# turbo.net
KiCad netlist of a schematic drawn in EAGLE
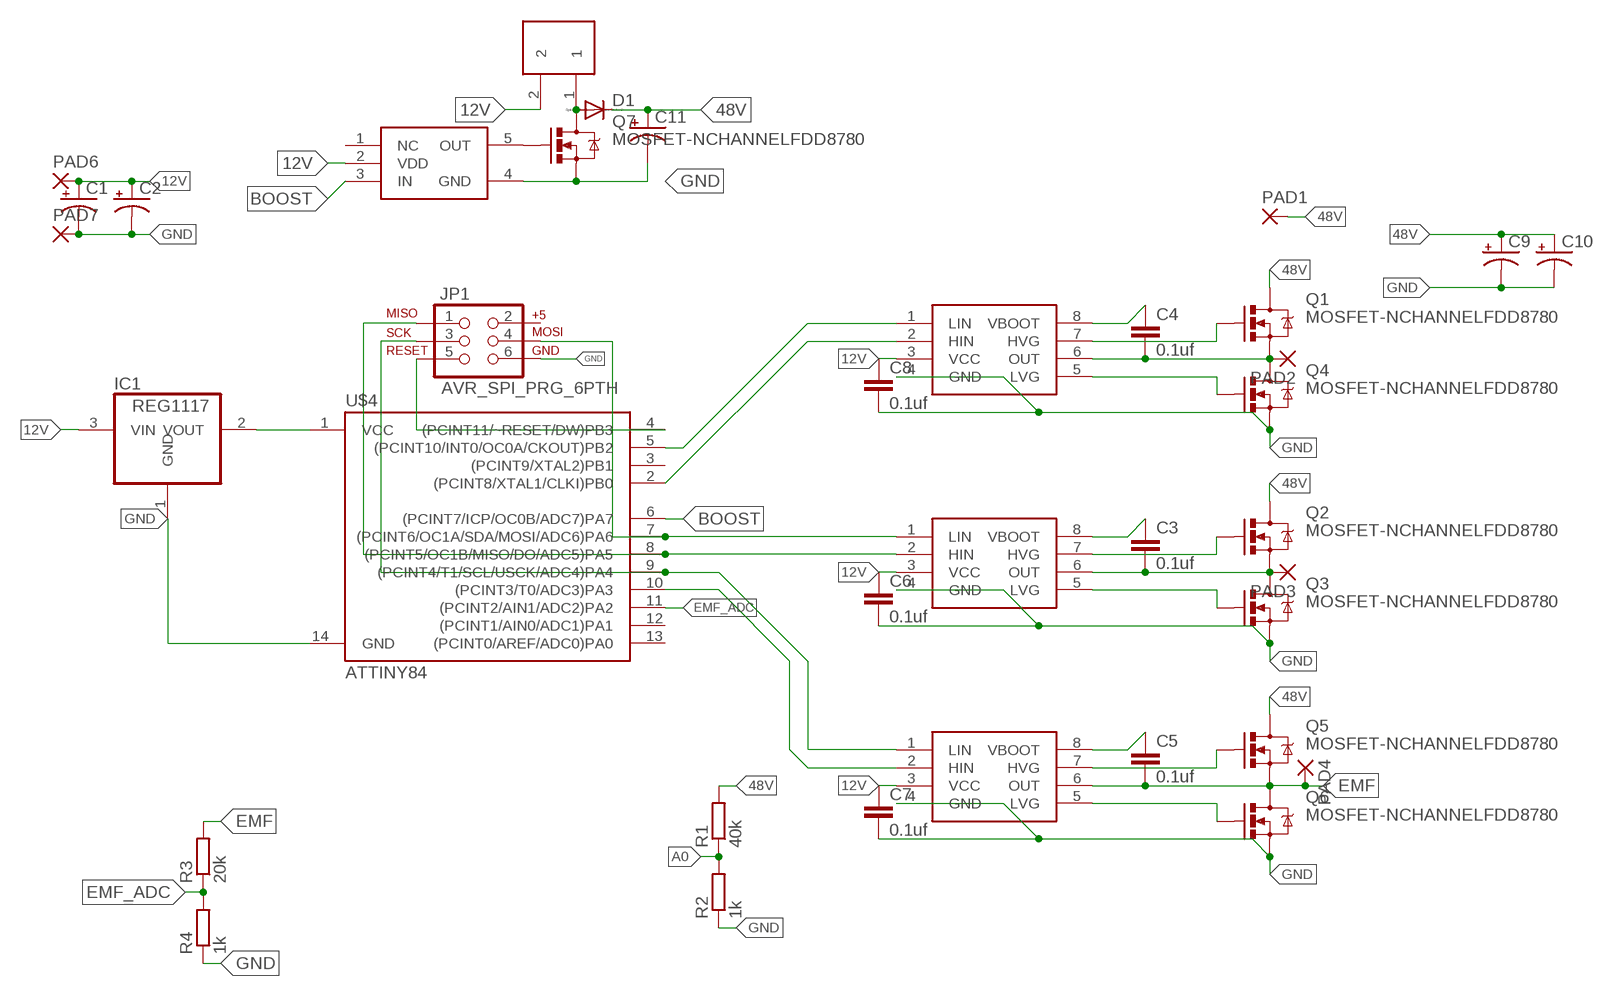
[diagram p0: schematic, sheet 1]

(export (version "E")
  (design (tool "Eeschema 10.0.6"))
  (components
    (comp (ref "C1")
      (value "CPOL-USE7.5-18")
      (footprint "eagle-import:E7,5-18")
      (libsource (lib "eagle-import") (part "CPOL-USE7.5-18"))
    )
    (comp (ref "C2")
      (value "CPOL-USE7.5-18")
      (footprint "eagle-import:E7,5-18")
      (libsource (lib "eagle-import") (part "CPOL-USE7.5-18"))
    )
    (comp (ref "C3")
      (value "0.1uf")
      (footprint "eagle-import:C0603")
      (libsource (lib "eagle-import") (part "C-EUC0603"))
    )
    (comp (ref "C4")
      (value "0.1uf")
      (footprint "eagle-import:C0603")
      (libsource (lib "eagle-import") (part "C-EUC0603"))
    )
    (comp (ref "C5")
      (value "0.1uf")
      (footprint "eagle-import:C0603")
      (libsource (lib "eagle-import") (part "C-EUC0603"))
    )
    (comp (ref "C6")
      (value "0.1uf")
      (footprint "eagle-import:C0603")
      (libsource (lib "eagle-import") (part "C-EUC0603"))
    )
    (comp (ref "C7")
      (value "0.1uf")
      (footprint "eagle-import:C0603")
      (libsource (lib "eagle-import") (part "C-EUC0603"))
    )
    (comp (ref "C8")
      (value "0.1uf")
      (footprint "eagle-import:C0603")
      (libsource (lib "eagle-import") (part "C-EUC0603"))
    )
    (comp (ref "C9")
      (value "CPOL-USE7.5-18")
      (footprint "eagle-import:E7,5-18")
      (libsource (lib "eagle-import") (part "CPOL-USE7.5-18"))
    )
    (comp (ref "C10")
      (value "CPOL-USE7.5-18")
      (footprint "eagle-import:E7,5-18")
      (libsource (lib "eagle-import") (part "CPOL-USE7.5-18"))
    )
    (comp (ref "C11")
      (value "CPOL-USE7.5-18")
      (footprint "eagle-import:E7,5-18")
      (libsource (lib "eagle-import") (part "CPOL-USE7.5-18"))
    )
    (comp (ref "D1")
      (value "DIODE-TO220V")
      (footprint "eagle-import:TO220ACS")
      (libsource (lib "eagle-import") (part "DIODE-TO220V"))
    )
    (comp (ref "IC1")
      (value "REG1117")
      (footprint "eagle-import:SOT223")
      (libsource (lib "eagle-import") (part "REG1117"))
    )
    (comp (ref "JP1")
      (value "AVR_SPI_PRG_6PTH")
      (footprint "eagle-import:2X3")
      (libsource (lib "eagle-import") (part "AVR_SPI_PRG_6PTH"))
    )
    (comp (ref "PAD1")
      (value "WIREPADSMD5-2,5")
      (footprint "eagle-import:5-2,5")
      (libsource (lib "eagle-import") (part "WIREPADSMD5-2,5"))
    )
    (comp (ref "PAD2")
      (value "WIREPADSMD5-2,5")
      (footprint "eagle-import:5-2,5")
      (libsource (lib "eagle-import") (part "WIREPADSMD5-2,5"))
    )
    (comp (ref "PAD3")
      (value "WIREPADSMD5-2,5")
      (footprint "eagle-import:5-2,5")
      (libsource (lib "eagle-import") (part "WIREPADSMD5-2,5"))
    )
    (comp (ref "PAD4")
      (value "WIREPADSMD5-2,5")
      (footprint "eagle-import:5-2,5")
      (libsource (lib "eagle-import") (part "WIREPADSMD5-2,5"))
    )
    (comp (ref "PAD6")
      (value "WIREPADSMD5-2,5")
      (footprint "eagle-import:5-2,5")
      (libsource (lib "eagle-import") (part "WIREPADSMD5-2,5"))
    )
    (comp (ref "PAD7")
      (value "WIREPADSMD5-2,5")
      (footprint "eagle-import:5-2,5")
      (libsource (lib "eagle-import") (part "WIREPADSMD5-2,5"))
    )
    (comp (ref "Q1")
      (value "MOSFET-NCHANNELFDD8780")
      (footprint "eagle-import:DPAK")
      (libsource (lib "eagle-import") (part "MOSFET-NCHANNELFDD8780"))
    )
    (comp (ref "Q2")
      (value "MOSFET-NCHANNELFDD8780")
      (footprint "eagle-import:DPAK")
      (libsource (lib "eagle-import") (part "MOSFET-NCHANNELFDD8780"))
    )
    (comp (ref "Q3")
      (value "MOSFET-NCHANNELFDD8780")
      (footprint "eagle-import:DPAK")
      (libsource (lib "eagle-import") (part "MOSFET-NCHANNELFDD8780"))
    )
    (comp (ref "Q4")
      (value "MOSFET-NCHANNELFDD8780")
      (footprint "eagle-import:DPAK")
      (libsource (lib "eagle-import") (part "MOSFET-NCHANNELFDD8780"))
    )
    (comp (ref "Q5")
      (value "MOSFET-NCHANNELFDD8780")
      (footprint "eagle-import:DPAK")
      (libsource (lib "eagle-import") (part "MOSFET-NCHANNELFDD8780"))
    )
    (comp (ref "Q6")
      (value "MOSFET-NCHANNELFDD8780")
      (footprint "eagle-import:DPAK")
      (libsource (lib "eagle-import") (part "MOSFET-NCHANNELFDD8780"))
    )
    (comp (ref "Q7")
      (value "MOSFET-NCHANNELFDD8780")
      (footprint "eagle-import:DPAK")
      (libsource (lib "eagle-import") (part "MOSFET-NCHANNELFDD8780"))
    )
    (comp (ref "R1")
      (value "40k")
      (footprint "eagle-import:R0603")
      (libsource (lib "eagle-import") (part "R-EU_R0603"))
    )
    (comp (ref "R2")
      (value "1k")
      (footprint "eagle-import:R0603")
      (libsource (lib "eagle-import") (part "R-EU_R0603"))
    )
    (comp (ref "R3")
      (value "20k")
      (footprint "eagle-import:R0603")
      (libsource (lib "eagle-import") (part "R-EU_R0603"))
    )
    (comp (ref "R4")
      (value "1k")
      (footprint "eagle-import:R0603")
      (libsource (lib "eagle-import") (part "R-EU_R0603"))
    )
    (comp (ref "U$1")
      (value "L6387")
      (footprint "eagle-import:SOIC8")
      (libsource (lib "eagle-import") (part "L6387"))
    )
    (comp (ref "U$2")
      (value "L6387")
      (footprint "eagle-import:SOIC8")
      (libsource (lib "eagle-import") (part "L6387"))
    )
    (comp (ref "U$3")
      (value "L6387")
      (footprint "eagle-import:SOIC8")
      (libsource (lib "eagle-import") (part "L6387"))
    )
    (comp (ref "U$4")
      (value "ATTINY84")
      (footprint "eagle-import:SO14")
      (libsource (lib "eagle-import") (part "ATTINY84"))
    )
    (comp (ref "U$5")
      (value "2310")
      (footprint "eagle-import:2310")
      (libsource (lib "eagle-import") (part "2310"))
    )
    (comp (ref "U$6")
      (value "MCP1415")
      (footprint "eagle-import:SOT23-5")
      (libsource (lib "eagle-import") (part "MCP1415"))
    )
  )
  (nets
    (net (code "1") (name "12V") (class "Default")
      (node (ref "C1") (pin "+") (pinfunction "+_+") (pintype "passive"))
      (node (ref "C2") (pin "+") (pinfunction "+_+") (pintype "passive"))
      (node (ref "C6") (pin "1") (pinfunction "1_1") (pintype "passive"))
      (node (ref "C7") (pin "1") (pinfunction "1_1") (pintype "passive"))
      (node (ref "C8") (pin "1") (pinfunction "1_1") (pintype "passive"))
      (node (ref "IC1") (pin "3") (pinfunction "VIN_3") (pintype "input"))
      (node (ref "PAD6") (pin "1") (pinfunction "P_1") (pintype "passive"))
      (node (ref "U$1") (pin "3") (pinfunction "VCC_3") (pintype "bidirectional"))
      (node (ref "U$2") (pin "3") (pinfunction "VCC_3") (pintype "bidirectional"))
      (node (ref "U$3") (pin "3") (pinfunction "VCC_3") (pintype "bidirectional"))
      (node (ref "U$5") (pin "2") (pinfunction "2_2") (pintype "bidirectional"))
      (node (ref "U$6") (pin "2") (pinfunction "VDD_2") (pintype "bidirectional"))
    )
    (net (code "2") (name "48V") (class "Default")
      (node (ref "C10") (pin "+") (pinfunction "+_+") (pintype "passive"))
      (node (ref "C11") (pin "+") (pinfunction "+_+") (pintype "passive"))
      (node (ref "C9") (pin "+") (pinfunction "+_+") (pintype "passive"))
      (node (ref "D1") (pin "C") (pinfunction "C_C") (pintype "passive"))
      (node (ref "PAD1") (pin "1") (pinfunction "P_1") (pintype "passive"))
      (node (ref "Q1") (pin "4") (pinfunction "D_4") (pintype "passive"))
      (node (ref "Q2") (pin "4") (pinfunction "D_4") (pintype "passive"))
      (node (ref "Q5") (pin "4") (pinfunction "D_4") (pintype "passive"))
      (node (ref "R1") (pin "2") (pinfunction "2_2") (pintype "passive"))
    )
    (net (code "3") (name "A0") (class "Default")
      (node (ref "R1") (pin "1") (pinfunction "1_1") (pintype "passive"))
      (node (ref "R2") (pin "2") (pinfunction "2_2") (pintype "passive"))
    )
    (net (code "4") (name "BOOST") (class "Default")
      (node (ref "U$4") (pin "6") (pinfunction "(PCINT7/ICP/OC0B/ADC7)PA7_6") (pintype "bidirectional"))
      (node (ref "U$6") (pin "3") (pinfunction "IN_3") (pintype "bidirectional"))
    )
    (net (code "5") (name "EMF") (class "Default")
      (node (ref "C5") (pin "2") (pinfunction "2_2") (pintype "passive"))
      (node (ref "PAD4") (pin "1") (pinfunction "P_1") (pintype "passive"))
      (node (ref "Q5") (pin "3") (pinfunction "S_3") (pintype "passive"))
      (node (ref "Q6") (pin "4") (pinfunction "D_4") (pintype "passive"))
      (node (ref "R3") (pin "2") (pinfunction "2_2") (pintype "passive"))
      (node (ref "U$3") (pin "6") (pinfunction "OUT_6") (pintype "bidirectional"))
    )
    (net (code "6") (name "EMF_ADC") (class "Default")
      (node (ref "R3") (pin "1") (pinfunction "1_1") (pintype "passive"))
      (node (ref "R4") (pin "2") (pinfunction "2_2") (pintype "passive"))
      (node (ref "U$4") (pin "11") (pinfunction "(PCINT2/AIN1/ADC2)PA2_11") (pintype "bidirectional"))
    )
    (net (code "7") (name "GND") (class "Default")
      (node (ref "C1") (pin "-") (pinfunction "-_-") (pintype "passive"))
      (node (ref "C10") (pin "-") (pinfunction "-_-") (pintype "passive"))
      (node (ref "C11") (pin "-") (pinfunction "-_-") (pintype "passive"))
      (node (ref "C2") (pin "-") (pinfunction "-_-") (pintype "passive"))
      (node (ref "C6") (pin "2") (pinfunction "2_2") (pintype "passive"))
      (node (ref "C7") (pin "2") (pinfunction "2_2") (pintype "passive"))
      (node (ref "C8") (pin "2") (pinfunction "2_2") (pintype "passive"))
      (node (ref "C9") (pin "-") (pinfunction "-_-") (pintype "passive"))
      (node (ref "IC1") (pin "1") (pinfunction "GND_1") (pintype "power_in"))
      (node (ref "JP1") (pin "6") (pinfunction "6_6") (pintype "passive"))
      (node (ref "PAD7") (pin "1") (pinfunction "P_1") (pintype "passive"))
      (node (ref "Q3") (pin "3") (pinfunction "S_3") (pintype "passive"))
      (node (ref "Q4") (pin "3") (pinfunction "S_3") (pintype "passive"))
      (node (ref "Q6") (pin "3") (pinfunction "S_3") (pintype "passive"))
      (node (ref "Q7") (pin "3") (pinfunction "S_3") (pintype "passive"))
      (node (ref "R2") (pin "1") (pinfunction "1_1") (pintype "passive"))
      (node (ref "R4") (pin "1") (pinfunction "1_1") (pintype "passive"))
      (node (ref "U$1") (pin "4") (pinfunction "GND_4") (pintype "bidirectional"))
      (node (ref "U$2") (pin "4") (pinfunction "GND_4") (pintype "bidirectional"))
      (node (ref "U$3") (pin "4") (pinfunction "GND_4") (pintype "bidirectional"))
      (node (ref "U$4") (pin "14") (pinfunction "GND_14") (pintype "bidirectional"))
      (node (ref "U$6") (pin "4") (pinfunction "GND_4") (pintype "bidirectional"))
    )
    (net (code "8") (name "Net-(IC1-VOUT)") (class "Default")
      (node (ref "IC1") (pin "2") (pinfunction "VOUT_2") (pintype "output"))
      (node (ref "U$4") (pin "1") (pinfunction "VCC_1") (pintype "bidirectional"))
    )
    (net (code "9") (name "Net-(PAD2-P)") (class "Default")
      (node (ref "C4") (pin "2") (pinfunction "2_2") (pintype "passive"))
      (node (ref "PAD2") (pin "1") (pinfunction "P_1") (pintype "passive"))
      (node (ref "Q1") (pin "3") (pinfunction "S_3") (pintype "passive"))
      (node (ref "Q4") (pin "4") (pinfunction "D_4") (pintype "passive"))
      (node (ref "U$1") (pin "6") (pinfunction "OUT_6") (pintype "bidirectional"))
    )
    (net (code "10") (name "Net-(PAD3-P)") (class "Default")
      (node (ref "C3") (pin "2") (pinfunction "2_2") (pintype "passive"))
      (node (ref "PAD3") (pin "1") (pinfunction "P_1") (pintype "passive"))
      (node (ref "Q2") (pin "3") (pinfunction "S_3") (pintype "passive"))
      (node (ref "Q3") (pin "4") (pinfunction "D_4") (pintype "passive"))
      (node (ref "U$2") (pin "6") (pinfunction "OUT_6") (pintype "bidirectional"))
    )
    (net (code "11") (name "Net-(Q1-G)") (class "Default")
      (node (ref "Q1") (pin "1") (pinfunction "G_1") (pintype "passive"))
      (node (ref "U$1") (pin "7") (pinfunction "HVG_7") (pintype "bidirectional"))
    )
    (net (code "12") (name "Net-(Q2-G)") (class "Default")
      (node (ref "Q2") (pin "1") (pinfunction "G_1") (pintype "passive"))
      (node (ref "U$2") (pin "7") (pinfunction "HVG_7") (pintype "bidirectional"))
    )
    (net (code "13") (name "Net-(Q3-G)") (class "Default")
      (node (ref "Q3") (pin "1") (pinfunction "G_1") (pintype "passive"))
      (node (ref "U$2") (pin "5") (pinfunction "LVG_5") (pintype "bidirectional"))
    )
    (net (code "14") (name "Net-(Q4-G)") (class "Default")
      (node (ref "Q4") (pin "1") (pinfunction "G_1") (pintype "passive"))
      (node (ref "U$1") (pin "5") (pinfunction "LVG_5") (pintype "bidirectional"))
    )
    (net (code "15") (name "Net-(Q5-G)") (class "Default")
      (node (ref "Q5") (pin "1") (pinfunction "G_1") (pintype "passive"))
      (node (ref "U$3") (pin "7") (pinfunction "HVG_7") (pintype "bidirectional"))
    )
    (net (code "16") (name "Net-(Q6-G)") (class "Default")
      (node (ref "Q6") (pin "1") (pinfunction "G_1") (pintype "passive"))
      (node (ref "U$3") (pin "5") (pinfunction "LVG_5") (pintype "bidirectional"))
    )
    (net (code "17") (name "Net-(Q7-D)") (class "Default")
      (node (ref "D1") (pin "A") (pinfunction "A_A") (pintype "passive"))
      (node (ref "Q7") (pin "4") (pinfunction "D_4") (pintype "passive"))
      (node (ref "U$5") (pin "1") (pinfunction "1_1") (pintype "bidirectional"))
    )
    (net (code "18") (name "Net-(Q7-G)") (class "Default")
      (node (ref "Q7") (pin "1") (pinfunction "G_1") (pintype "passive"))
      (node (ref "U$6") (pin "5") (pinfunction "OUT_5") (pintype "bidirectional"))
    )
    (net (code "19") (name "Net-(U$1-HIN)") (class "Default")
      (node (ref "U$1") (pin "2") (pinfunction "HIN_2") (pintype "bidirectional"))
      (node (ref "U$4") (pin "2") (pinfunction "(PCINT8/XTAL1/CLKI)PB0_2") (pintype "bidirectional"))
    )
    (net (code "20") (name "Net-(U$1-LIN)") (class "Default")
      (node (ref "U$1") (pin "1") (pinfunction "LIN_1") (pintype "bidirectional"))
      (node (ref "U$4") (pin "5") (pinfunction "(PCINT10/INT0/OC0A/CKOUT)PB2_5") (pintype "bidirectional"))
    )
    (net (code "21") (name "Net-(U$1-VBOOT)") (class "Default")
      (node (ref "C4") (pin "1") (pinfunction "1_1") (pintype "passive"))
      (node (ref "U$1") (pin "8") (pinfunction "VBOOT_8") (pintype "bidirectional"))
    )
    (net (code "22") (name "Net-(U$2-HIN)") (class "Default")
      (node (ref "JP1") (pin "1") (pinfunction "1_1") (pintype "passive"))
      (node (ref "U$2") (pin "2") (pinfunction "HIN_2") (pintype "bidirectional"))
      (node (ref "U$4") (pin "8") (pinfunction "(PCINT5/OC1B/MISO/DO/ADC5)PA5_8") (pintype "bidirectional"))
    )
    (net (code "23") (name "Net-(U$2-LIN)") (class "Default")
      (node (ref "JP1") (pin "4") (pinfunction "4_4") (pintype "passive"))
      (node (ref "U$2") (pin "1") (pinfunction "LIN_1") (pintype "bidirectional"))
      (node (ref "U$4") (pin "7") (pinfunction "(PCINT6/OC1A/SDA/MOSI/ADC6)PA6_7") (pintype "bidirectional"))
    )
    (net (code "24") (name "Net-(U$2-VBOOT)") (class "Default")
      (node (ref "C3") (pin "1") (pinfunction "1_1") (pintype "passive"))
      (node (ref "U$2") (pin "8") (pinfunction "VBOOT_8") (pintype "bidirectional"))
    )
    (net (code "25") (name "Net-(U$3-HIN)") (class "Default")
      (node (ref "U$3") (pin "2") (pinfunction "HIN_2") (pintype "bidirectional"))
      (node (ref "U$4") (pin "10") (pinfunction "(PCINT3/T0/ADC3)PA3_10") (pintype "bidirectional"))
    )
    (net (code "26") (name "Net-(U$3-LIN)") (class "Default")
      (node (ref "JP1") (pin "3") (pinfunction "3_3") (pintype "passive"))
      (node (ref "U$3") (pin "1") (pinfunction "LIN_1") (pintype "bidirectional"))
      (node (ref "U$4") (pin "9") (pinfunction "(PCINT4/T1/SCL/USCK/ADC4)PA4_9") (pintype "bidirectional"))
    )
    (net (code "27") (name "Net-(U$3-VBOOT)") (class "Default")
      (node (ref "C5") (pin "1") (pinfunction "1_1") (pintype "passive"))
      (node (ref "U$3") (pin "8") (pinfunction "VBOOT_8") (pintype "bidirectional"))
    )
    (net (code "28") (name "Net-(U$4-(PCINT11{slash}~{RESET{slash}DW})PB3)") (class "Default")
      (node (ref "JP1") (pin "5") (pinfunction "5_5") (pintype "passive"))
      (node (ref "U$4") (pin "4") (pinfunction "(PCINT11/~{RESET/DW})PB3_4") (pintype "bidirectional"))
    )
    (net (code "29") (name "unconnected-(JP1-Pad2)") (class "Default")
      (node (ref "JP1") (pin "2") (pinfunction "2_2") (pintype "passive"))
    )
    (net (code "30") (name "unconnected-(U$4-(PCINT0{slash}AREF{slash}ADC0)PA0-Pad13)") (class "Default")
      (node (ref "U$4") (pin "13") (pinfunction "(PCINT0/AREF/ADC0)PA0_13") (pintype "bidirectional"))
    )
    (net (code "31") (name "unconnected-(U$4-(PCINT1{slash}AIN0{slash}ADC1)PA1-Pad12)") (class "Default")
      (node (ref "U$4") (pin "12") (pinfunction "(PCINT1/AIN0/ADC1)PA1_12") (pintype "bidirectional"))
    )
    (net (code "32") (name "unconnected-(U$4-(PCINT9{slash}XTAL2)PB1-Pad3)") (class "Default")
      (node (ref "U$4") (pin "3") (pinfunction "(PCINT9/XTAL2)PB1_3") (pintype "bidirectional"))
    )
    (net (code "33") (name "unconnected-(U$6-NC-Pad1)") (class "Default")
      (node (ref "U$6") (pin "1") (pinfunction "NC_1") (pintype "bidirectional"))
    )
  )
)
